# CAN_module.net
KiCad netlist of a schematic drawn in Altium Designer
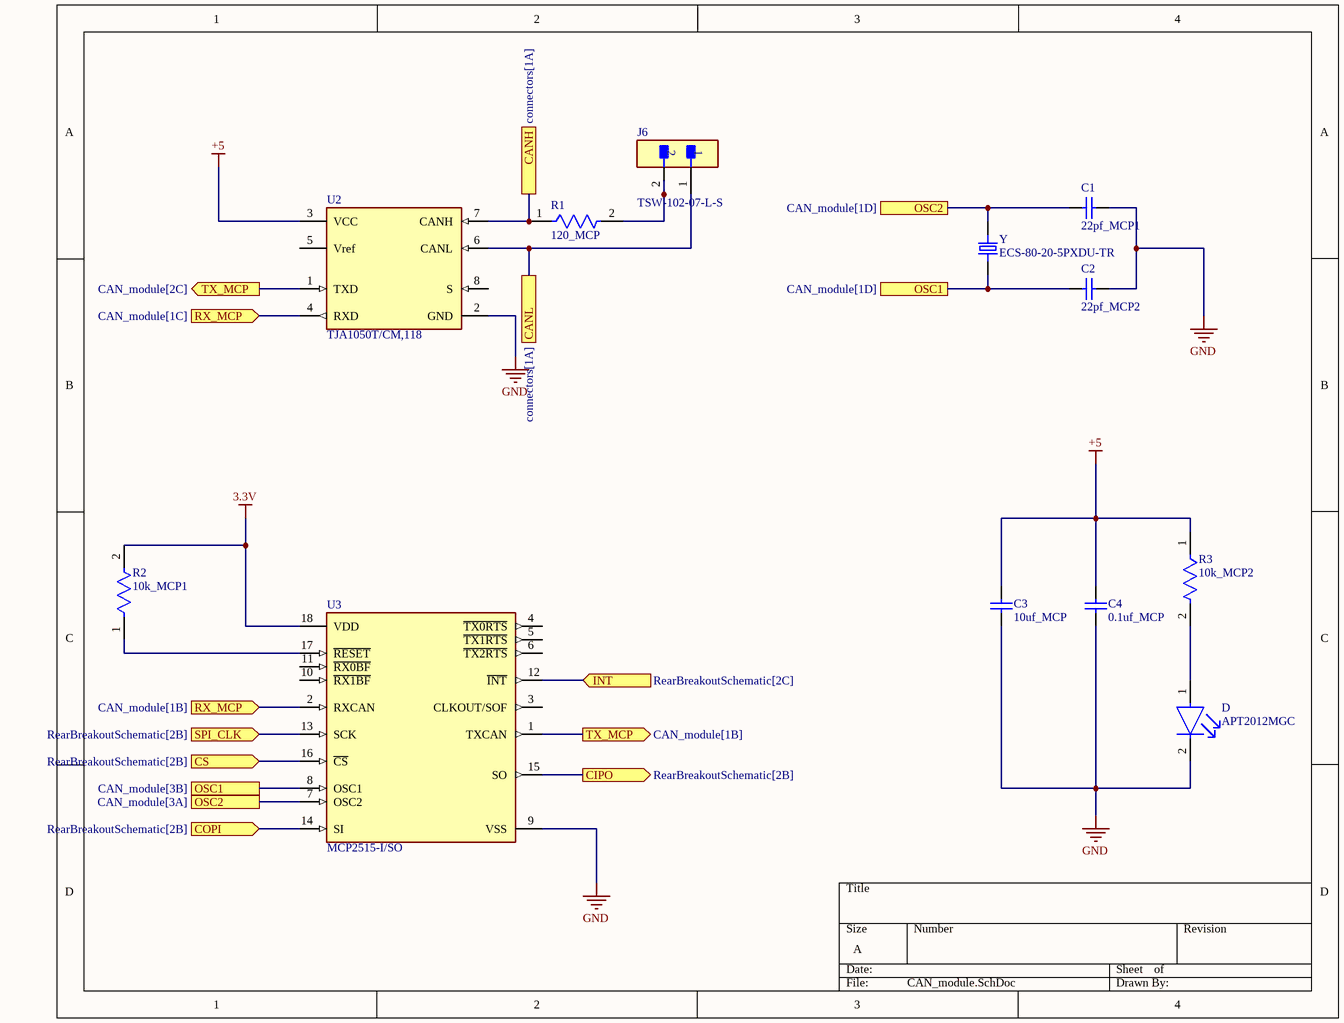
[diagram p0: CAN_module.SchDoc]

(export (version "E")
  (design (tool "Eeschema 10.0.6"))
  (components
    (comp (ref "C1")
      (value "22pf_MCP1")
      (footprint "CAPC2013X145X50NL20T20")
      (fields (field (name "MANUFACTURER") "Vitramon") (field (name "PART NUMBER") "VJ0805A220GXXCW1BC"))
      (libsource (lib "Altium Content Vault") (part "CAP"))
    )
    (comp (ref "C2")
      (value "22pf_MCP2")
      (footprint "CAPC2013X145X50NL20T20")
      (fields (field (name "MANUFACTURER") "Vitramon") (field (name "PART NUMBER") "VJ0805A220GXXCW1BC"))
      (libsource (lib "Altium Content Vault") (part "CAP"))
    )
    (comp (ref "C3")
      (value "10uf_MCP")
      (footprint "CAPC2013X145X50NL20T20")
      (fields (field (name "MANUFACTURER") "Vitramon") (field (name "PART NUMBER") "VJ0805A220GXXCW1BC"))
      (libsource (lib "Altium Content Vault") (part "CAP"))
    )
    (comp (ref "C4")
      (value "0.1uf_MCP")
      (footprint "CAPC2013X145X50NL20T20")
      (fields (field (name "MANUFACTURER") "Vitramon") (field (name "PART NUMBER") "VJ0805A220GXXCW1BC"))
      (libsource (lib "Altium Content Vault") (part "CAP"))
    )
    (comp (ref "D")
      (value "APT2012MGC")
      (footprint "FP-APT2012MGC-MFG")
      (description "LED GREEN CLEAR CHIP SMD")
      (libsource (lib "Altium Content Vault") (part "ab1c01a81903e929fc6c44469aada92"))
    )
    (comp (ref "J6")
      (value "TSW-102-07-L-S")
      (footprint "FP-TSW-102-07-L-S-MFG")
      (description "CONN HEADER VERT 2POS 2.54MM")
      (libsource (lib "Altium Content Vault") (part "3bc925449376181038e59eaffc5286c"))
    )
    (comp (ref "R1")
      (value "120_MCP")
      (footprint "FP-CRCW0805-e3-IPC_C")
      (description "RES Thick Film, 4.02Ω, 1%, 0.125W, 200ppm/°C, 0805")
      (fields (field (name "TOLERANCE") "1%"))
      (libsource (lib "Altium Content Vault") (part "1029c3af85768c4190bb7ad29bc67b5"))
    )
    (comp (ref "R2")
      (value "10k_MCP1")
      (footprint "FP-CRCW0805-e3-IPC_C")
      (description "RES Thick Film, 4.02Ω, 1%, 0.125W, 200ppm/°C, 0805")
      (fields (field (name "TOLERANCE") "1%"))
      (libsource (lib "Altium Content Vault") (part "1029c3af85768c4190bb7ad29bc67b5"))
    )
    (comp (ref "R3")
      (value "10k_MCP2")
      (footprint "FP-CRCW0805-e3-IPC_C")
      (description "RES Thick Film, 4.02Ω, 1%, 0.125W, 200ppm/°C, 0805")
      (fields (field (name "TOLERANCE") "1%"))
      (libsource (lib "Altium Content Vault") (part "1029c3af85768c4190bb7ad29bc67b5"))
    )
    (comp (ref "U2")
      (value "TJA1050T/CM,118")
      (footprint "FP-SOT96-1-IPC_A")
      (description "IC TRANSCEIVER HALF 1/1 8SO")
      (libsource (lib "Altium Content Vault") (part "cfdefafd38a55dc0607790f57b8a78f"))
    )
    (comp (ref "U3")
      (value "MCP2515-I/SO")
      (footprint "FP-C04-051-MFG")
      (description "IC CAN CONTROLLER W/SPI 18SOIC")
      (fields
        (field (name "MANUFACTURER") "Microchip")
        (field (name "OCTOPART") "https://octopart.com/mcp2515-i%2Fso-microchip-430187")
      )
      (libsource (lib "Altium Content Vault") (part "1c78ea6ff576bac94664e2637e1b479"))
    )
    (comp (ref "Y")
      (value "ECS-80-20-5PXDU-TR")
      (footprint "XTAL_ECS-80-20-5PXDU-TR")
      (description "8MHz Â±30ppm Crystal 20pF 60 Ohms HC-49/US")
      (fields (field (name "MF") "ECS Inc."))
      (libsource (lib "ECS-80-20-5PXDU-TR") (part "ECS-80-20-5PXDU-TR"))
    )
  )
  (nets
    (net (code "1") (name "+5") (class "Default")
      (node (ref "C3") (pin "2") (pinfunction "2_2") (pintype "passive"))
      (node (ref "C4") (pin "2") (pinfunction "2_2") (pintype "passive"))
      (node (ref "R3") (pin "1") (pinfunction "1_1") (pintype "passive"))
      (node (ref "U2") (pin "3") (pinfunction "VCC_3") (pintype "power_in"))
    )
    (net (code "2") (name "/CANH") (class "Default")
      (node (ref "R1") (pin "1") (pinfunction "1_1") (pintype "passive"))
      (node (ref "U2") (pin "7") (pinfunction "CANH_7") (pintype "input"))
    )
    (net (code "3") (name "/CANL") (class "Default")
      (node (ref "J6") (pin "1") (pinfunction "1_1") (pintype "passive"))
      (node (ref "U2") (pin "6") (pinfunction "CANL_6") (pintype "input"))
    )
    (net (code "4") (name "/CIPO") (class "Default")
      (node (ref "U3") (pin "15") (pinfunction "SO_15") (pintype "output"))
    )
    (net (code "5") (name "/COPI") (class "Default")
      (node (ref "U3") (pin "14") (pinfunction "SI_14") (pintype "input"))
    )
    (net (code "6") (name "/CS") (class "Default")
      (node (ref "U3") (pin "16") (pinfunction "~{CS}_16") (pintype "input"))
    )
    (net (code "7") (name "/INT") (class "Default")
      (node (ref "U3") (pin "12") (pinfunction "~{INT}_12") (pintype "output"))
    )
    (net (code "8") (name "/OSC1") (class "Default")
      (node (ref "C2") (pin "1") (pinfunction "1_1") (pintype "passive"))
      (node (ref "U3") (pin "8") (pinfunction "OSC1_8") (pintype "input"))
      (node (ref "Y") (pin "1") (pinfunction "1_1") (pintype "passive"))
    )
    (net (code "9") (name "/OSC2") (class "Default")
      (node (ref "C1") (pin "1") (pinfunction "1_1") (pintype "passive"))
      (node (ref "U3") (pin "7") (pinfunction "OSC2_7") (pintype "input"))
      (node (ref "Y") (pin "2") (pinfunction "2_2") (pintype "passive"))
    )
    (net (code "10") (name "/RX_MCP") (class "Default")
      (node (ref "U2") (pin "4") (pinfunction "RXD_4") (pintype "output"))
      (node (ref "U3") (pin "2") (pinfunction "RXCAN_2") (pintype "input"))
    )
    (net (code "11") (name "/SPI_CLK") (class "Default")
      (node (ref "U3") (pin "13") (pinfunction "SCK_13") (pintype "input"))
    )
    (net (code "12") (name "/TX_MCP") (class "Default")
      (node (ref "U2") (pin "1") (pinfunction "TXD_1") (pintype "input"))
      (node (ref "U3") (pin "1") (pinfunction "TXCAN_1") (pintype "output"))
    )
    (net (code "13") (name "3.3V") (class "Default")
      (node (ref "R2") (pin "2") (pinfunction "2_2") (pintype "passive"))
      (node (ref "U3") (pin "18") (pinfunction "VDD_18") (pintype "power_in"))
    )
    (net (code "14") (name "GND") (class "Default")
      (node (ref "C1") (pin "2") (pinfunction "2_2") (pintype "passive"))
      (node (ref "C2") (pin "2") (pinfunction "2_2") (pintype "passive"))
      (node (ref "C3") (pin "1") (pinfunction "1_1") (pintype "passive"))
      (node (ref "C4") (pin "1") (pinfunction "1_1") (pintype "passive"))
      (node (ref "D") (pin "2") (pinfunction "C_2") (pintype "passive"))
      (node (ref "U2") (pin "2") (pinfunction "GND_2") (pintype "power_in"))
      (node (ref "U3") (pin "9") (pinfunction "VSS_9") (pintype "power_in"))
    )
    (net (code "15") (name "Net-(D-A)") (class "Default")
      (node (ref "D") (pin "1") (pinfunction "A_1") (pintype "passive"))
      (node (ref "R3") (pin "2") (pinfunction "2_2") (pintype "passive"))
    )
    (net (code "16") (name "Net-(J6-Pad2)") (class "Default")
      (node (ref "J6") (pin "2") (pinfunction "2_2") (pintype "passive"))
      (node (ref "R1") (pin "2") (pinfunction "2_2") (pintype "passive"))
    )
    (net (code "17") (name "Net-(U3-~{RESET})") (class "Default")
      (node (ref "R2") (pin "1") (pinfunction "1_1") (pintype "passive"))
      (node (ref "U3") (pin "17") (pinfunction "~{RESET}_17") (pintype "input"))
    )
    (net (code "18") (name "unconnected-(U2-S-Pad8)") (class "Default")
      (node (ref "U2") (pin "8") (pinfunction "S_8") (pintype "input"))
    )
    (net (code "19") (name "unconnected-(U2-Vref-Pad5)") (class "Default")
      (node (ref "U2") (pin "5") (pinfunction "Vref_5") (pintype "power_in"))
    )
    (net (code "20") (name "unconnected-(U3-CLKOUT{slash}SOF-Pad3)") (class "Default")
      (node (ref "U3") (pin "3") (pinfunction "CLKOUT/SOF_3") (pintype "output"))
    )
    (net (code "21") (name "unconnected-(U3-~{RX0BF}-Pad11)") (class "Default")
      (node (ref "U3") (pin "11") (pinfunction "~{RX0BF}_11") (pintype "input"))
    )
    (net (code "22") (name "unconnected-(U3-~{RX1BF}-Pad10)") (class "Default")
      (node (ref "U3") (pin "10") (pinfunction "~{RX1BF}_10") (pintype "input"))
    )
    (net (code "23") (name "unconnected-(U3-~{TX0RTS}-Pad4)") (class "Default")
      (node (ref "U3") (pin "4") (pinfunction "~{TX0RTS}_4") (pintype "output"))
    )
    (net (code "24") (name "unconnected-(U3-~{TX1RTS}-Pad5)") (class "Default")
      (node (ref "U3") (pin "5") (pinfunction "~{TX1RTS}_5") (pintype "output"))
    )
    (net (code "25") (name "unconnected-(U3-~{TX2RTS}-Pad6)") (class "Default")
      (node (ref "U3") (pin "6") (pinfunction "~{TX2RTS}_6") (pintype "output"))
    )
  )
)
